# MECHWARFARE_BOARD.net
KiCad netlist of a schematic drawn in EAGLE
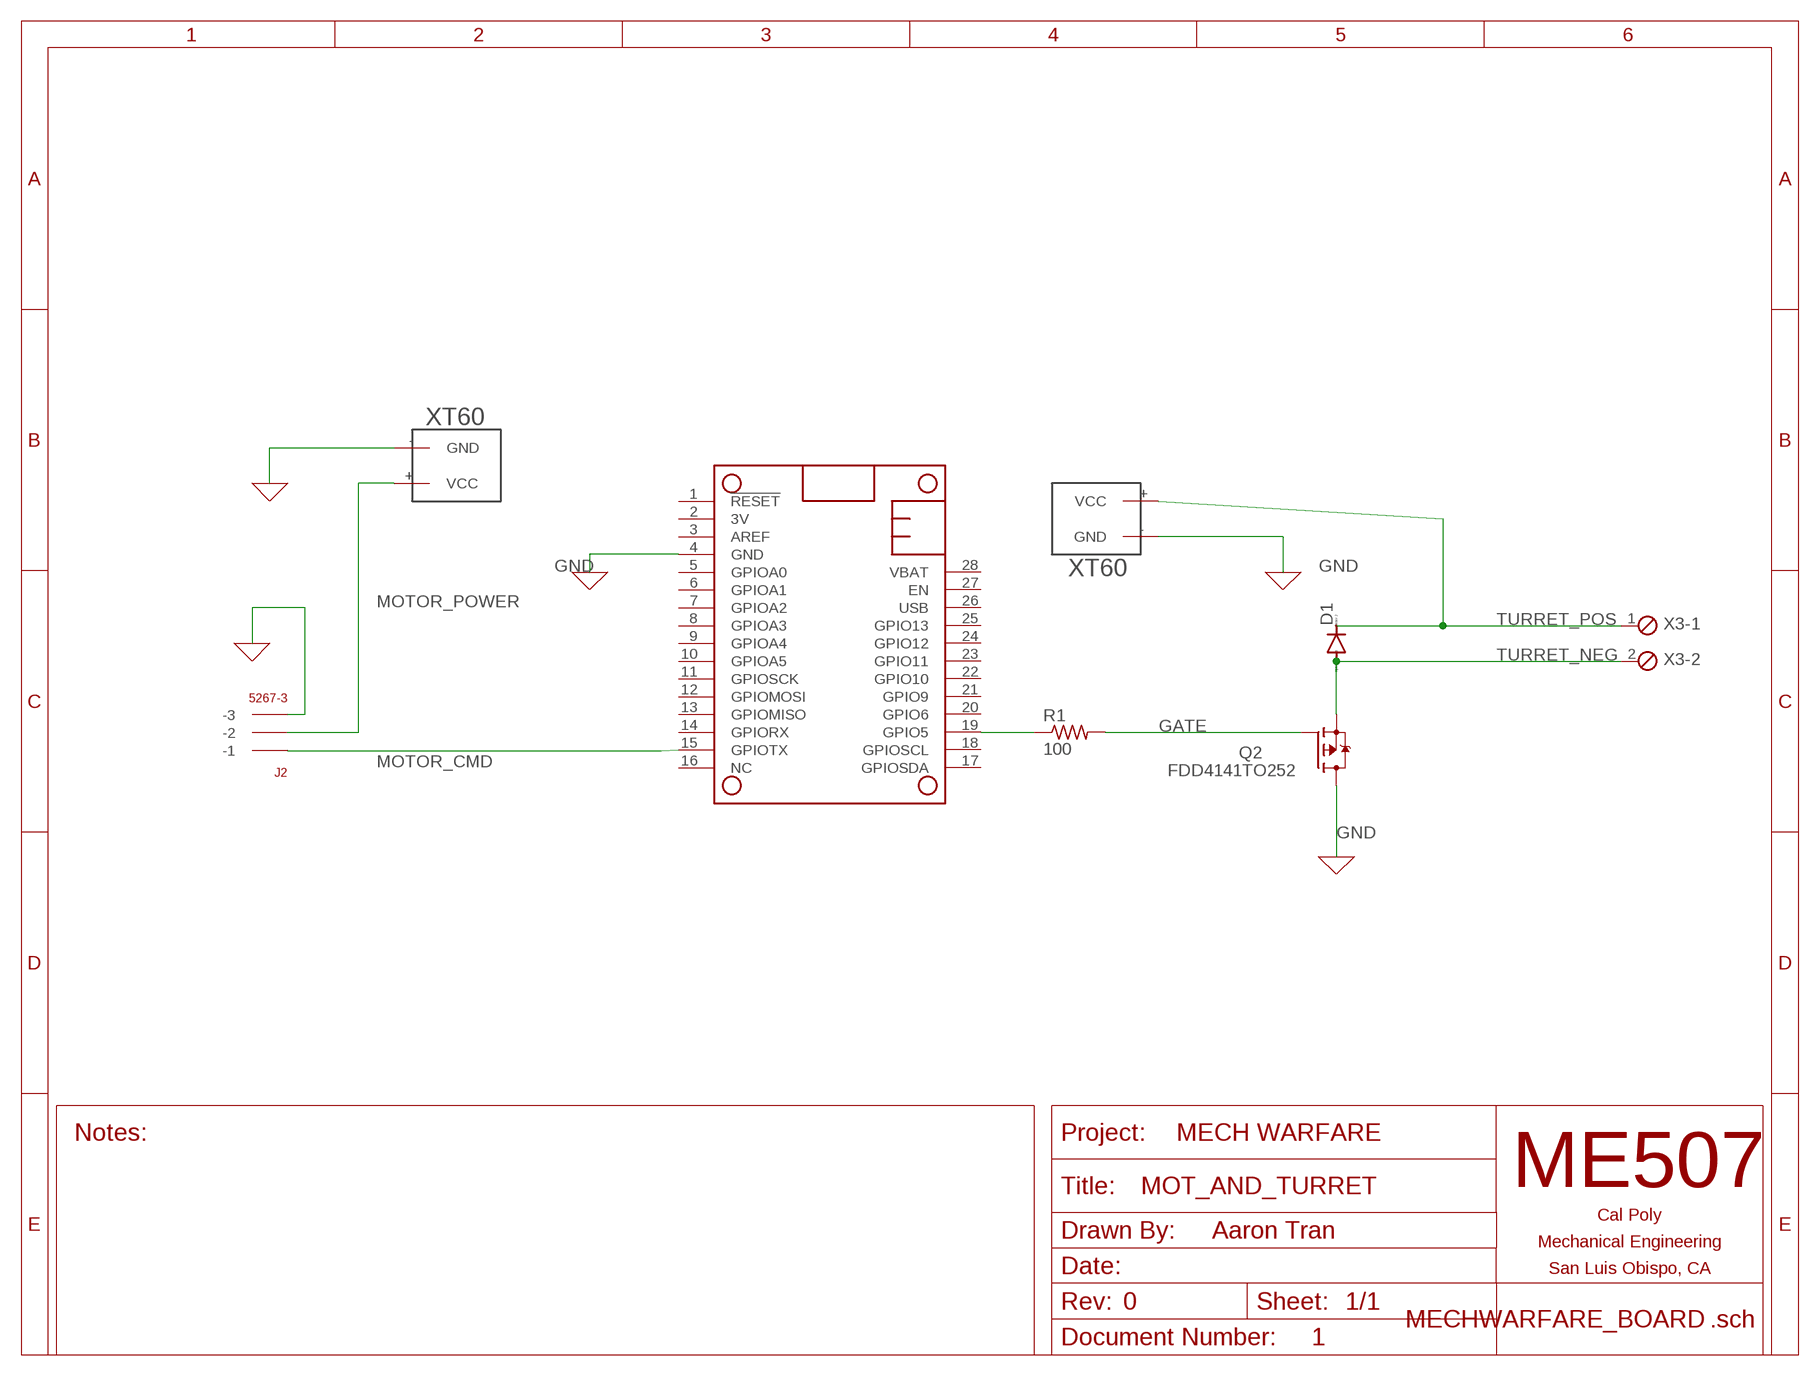
[diagram p0: schematic, sheet 1]

(export (version "E")
  (design (tool "Eeschema 10.0.6"))
  (components
    (comp (ref "D1")
      (value "DIODE-DO-214AC")
      (footprint "eagle-import:DO-214AC")
      (libsource (lib "eagle-import") (part "DIODE-DO-214AC"))
    )
    (comp (ref "J2")
      (value "5267-3")
      (footprint "eagle-import:5267-3")
      (libsource (lib "eagle-import") (part "5267-3"))
    )
    (comp (ref "MS2")
      (value "FEATHERWINGEXTENDED_BOTH_ENDS")
      (footprint "eagle-import:FEATHERWING")
      (libsource (lib "eagle-import") (part "FEATHERWINGEXTENDED_BOTH_ENDS"))
    )
    (comp (ref "Q2")
      (value "FDD4141TO252")
      (footprint "eagle-import:TO252")
      (libsource (lib "eagle-import") (part "FDD4141TO252"))
    )
    (comp (ref "R1")
      (value "100")
      (footprint "eagle-import:R0805")
      (libsource (lib "eagle-import") (part "R-US_R0805"))
    )
    (comp (ref "U$1")
      (value "XT60")
      (footprint "eagle-import:XT60")
      (libsource (lib "eagle-import") (part "XT60"))
    )
    (comp (ref "U$2")
      (value "XT60")
      (footprint "eagle-import:XT60")
      (libsource (lib "eagle-import") (part "XT60"))
    )
    (comp (ref "X3")
      (value "SCREWTERM_2P_254")
      (footprint "eagle-import:2POL254")
      (libsource (lib "eagle-import") (part "SCREWTERM_2P_254"))
    )
  )
  (nets
    (net (code "1") (name "/3V") (class "Default")
      (node (ref "MS2") (pin "2") (pinfunction "3V_2") (pintype "power_in"))
    )
    (net (code "2") (name "/GATE") (class "Default")
      (node (ref "Q2") (pin "1") (pinfunction "G_1") (pintype "passive"))
      (node (ref "R1") (pin "2") (pinfunction "2_2") (pintype "passive"))
    )
    (net (code "3") (name "/MOTOR_CMD") (class "Default")
      (node (ref "J2") (pin "P$1") (pinfunction "-1_P$1") (pintype "bidirectional"))
      (node (ref "MS2") (pin "15") (pinfunction "GPIOTX_15") (pintype "bidirectional"))
    )
    (net (code "4") (name "/MOTOR_POWER") (class "Default")
      (node (ref "J2") (pin "P$2") (pinfunction "-2_P$2") (pintype "bidirectional"))
      (node (ref "U$1") (pin "+") (pinfunction "VCC_+") (pintype "bidirectional"))
    )
    (net (code "5") (name "/TURRET_NEG") (class "Default")
      (node (ref "D1") (pin "A") (pinfunction "A_A") (pintype "passive"))
      (node (ref "Q2") (pin "2") (pinfunction "S_2") (pintype "passive"))
      (node (ref "X3") (pin "2") (pinfunction "1_2") (pintype "passive"))
    )
    (net (code "6") (name "/TURRET_POS") (class "Default")
      (node (ref "D1") (pin "C") (pinfunction "C_C") (pintype "passive"))
      (node (ref "U$2") (pin "+") (pinfunction "VCC_+") (pintype "bidirectional"))
      (node (ref "X3") (pin "1") (pinfunction "1_1") (pintype "passive"))
    )
    (net (code "7") (name "/USB") (class "Default")
      (node (ref "MS2") (pin "26") (pinfunction "USB_26") (pintype "power_in"))
    )
    (net (code "8") (name "/VBAT") (class "Default")
      (node (ref "MS2") (pin "28") (pinfunction "VBAT_28") (pintype "power_in"))
    )
    (net (code "9") (name "GND") (class "Default")
      (node (ref "J2") (pin "P$3") (pinfunction "-3_P$3") (pintype "bidirectional"))
      (node (ref "MS2") (pin "4") (pinfunction "GND_4") (pintype "power_in"))
      (node (ref "Q2") (pin "3") (pinfunction "D_3") (pintype "passive"))
      (node (ref "U$1") (pin "-") (pinfunction "GND_-") (pintype "bidirectional"))
      (node (ref "U$2") (pin "-") (pinfunction "GND_-") (pintype "bidirectional"))
    )
    (net (code "10") (name "Net-(MS2-GPIO5)") (class "Default")
      (node (ref "MS2") (pin "19") (pinfunction "GPIO5_19") (pintype "bidirectional"))
      (node (ref "R1") (pin "1") (pinfunction "1_1") (pintype "passive"))
    )
    (net (code "11") (name "unconnected-(MS2-AREF-Pad3)") (class "Default")
      (node (ref "MS2") (pin "3") (pinfunction "AREF_3") (pintype "passive"))
    )
    (net (code "12") (name "unconnected-(MS2-EN-Pad27)") (class "Default")
      (node (ref "MS2") (pin "27") (pinfunction "EN_27") (pintype "passive"))
    )
    (net (code "13") (name "unconnected-(MS2-GPIO6-Pad20)") (class "Default")
      (node (ref "MS2") (pin "20") (pinfunction "GPIO6_20") (pintype "bidirectional"))
    )
    (net (code "14") (name "unconnected-(MS2-GPIO9-Pad21)") (class "Default")
      (node (ref "MS2") (pin "21") (pinfunction "GPIO9_21") (pintype "bidirectional"))
    )
    (net (code "15") (name "unconnected-(MS2-GPIO10-Pad22)") (class "Default")
      (node (ref "MS2") (pin "22") (pinfunction "GPIO10_22") (pintype "bidirectional"))
    )
    (net (code "16") (name "unconnected-(MS2-GPIO11-Pad23)") (class "Default")
      (node (ref "MS2") (pin "23") (pinfunction "GPIO11_23") (pintype "bidirectional"))
    )
    (net (code "17") (name "unconnected-(MS2-GPIO12-Pad24)") (class "Default")
      (node (ref "MS2") (pin "24") (pinfunction "GPIO12_24") (pintype "bidirectional"))
    )
    (net (code "18") (name "unconnected-(MS2-GPIO13-Pad25)") (class "Default")
      (node (ref "MS2") (pin "25") (pinfunction "GPIO13_25") (pintype "bidirectional"))
    )
    (net (code "19") (name "unconnected-(MS2-GPIOA0-Pad5)") (class "Default")
      (node (ref "MS2") (pin "5") (pinfunction "GPIOA0_5") (pintype "bidirectional"))
    )
    (net (code "20") (name "unconnected-(MS2-GPIOA1-Pad6)") (class "Default")
      (node (ref "MS2") (pin "6") (pinfunction "GPIOA1_6") (pintype "bidirectional"))
    )
    (net (code "21") (name "unconnected-(MS2-GPIOA2-Pad7)") (class "Default")
      (node (ref "MS2") (pin "7") (pinfunction "GPIOA2_7") (pintype "bidirectional"))
    )
    (net (code "22") (name "unconnected-(MS2-GPIOA3-Pad8)") (class "Default")
      (node (ref "MS2") (pin "8") (pinfunction "GPIOA3_8") (pintype "bidirectional"))
    )
    (net (code "23") (name "unconnected-(MS2-GPIOA4-Pad9)") (class "Default")
      (node (ref "MS2") (pin "9") (pinfunction "GPIOA4_9") (pintype "bidirectional"))
    )
    (net (code "24") (name "unconnected-(MS2-GPIOA5-Pad10)") (class "Default")
      (node (ref "MS2") (pin "10") (pinfunction "GPIOA5_10") (pintype "bidirectional"))
    )
    (net (code "25") (name "unconnected-(MS2-GPIOMISO-Pad13)") (class "Default")
      (node (ref "MS2") (pin "13") (pinfunction "GPIOMISO_13") (pintype "bidirectional"))
    )
    (net (code "26") (name "unconnected-(MS2-GPIOMOSI-Pad12)") (class "Default")
      (node (ref "MS2") (pin "12") (pinfunction "GPIOMOSI_12") (pintype "bidirectional"))
    )
    (net (code "27") (name "unconnected-(MS2-GPIORX-Pad14)") (class "Default")
      (node (ref "MS2") (pin "14") (pinfunction "GPIORX_14") (pintype "bidirectional"))
    )
    (net (code "28") (name "unconnected-(MS2-GPIOSCK-Pad11)") (class "Default")
      (node (ref "MS2") (pin "11") (pinfunction "GPIOSCK_11") (pintype "bidirectional"))
    )
    (net (code "29") (name "unconnected-(MS2-GPIOSCL-Pad18)") (class "Default")
      (node (ref "MS2") (pin "18") (pinfunction "GPIOSCL_18") (pintype "bidirectional"))
    )
    (net (code "30") (name "unconnected-(MS2-GPIOSDA-Pad17)") (class "Default")
      (node (ref "MS2") (pin "17") (pinfunction "GPIOSDA_17") (pintype "bidirectional"))
    )
    (net (code "31") (name "unconnected-(MS2-NC-Pad16)") (class "Default")
      (node (ref "MS2") (pin "16") (pinfunction "NC_16") (pintype "passive"))
    )
    (net (code "32") (name "unconnected-(MS2-~{RESET}-Pad1)") (class "Default")
      (node (ref "MS2") (pin "1") (pinfunction "~{RESET}_1") (pintype "input"))
    )
  )
)
